# wemosD1mini_noSDmodule.net
KiCad netlist of a schematic drawn in EAGLE
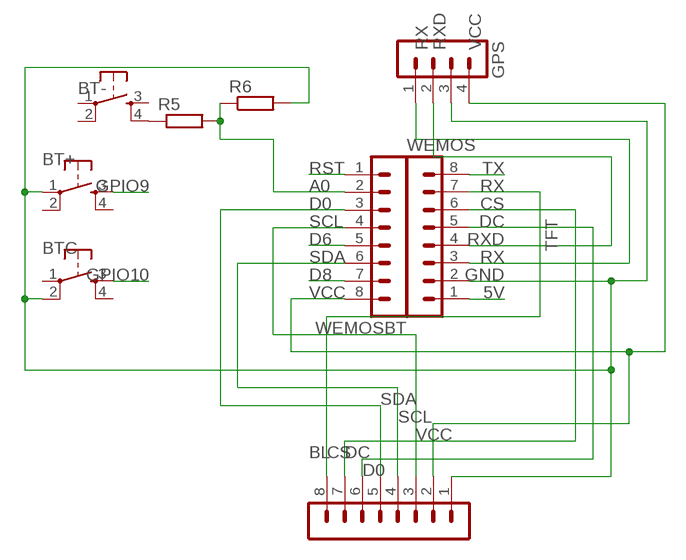
[diagram p0: schematic, sheet 1]

(export (version "E")
  (design (tool "Eeschema 10.0.6"))
  (components
    (comp (ref "BT+")
      (value "DTS-6")
      (footprint "eagle-import:DTS-6")
      (libsource (lib "eagle-import") (part "DTS-6"))
    )
    (comp (ref "BT-")
      (value "DTS-6")
      (footprint "eagle-import:DTS-6")
      (libsource (lib "eagle-import") (part "DTS-6"))
    )
    (comp (ref "BTC")
      (value "DTS-6")
      (footprint "eagle-import:DTS-6")
      (libsource (lib "eagle-import") (part "DTS-6"))
    )
    (comp (ref "GPS")
      (value "MA04-1")
      (footprint "eagle-import:MA04-1")
      (libsource (lib "eagle-import") (part "MA04-1"))
    )
    (comp (ref "R5")
      (value "R0207/10")
      (footprint "eagle-import:0207_10")
      (libsource (lib "eagle-import") (part "R0207/10"))
    )
    (comp (ref "R6")
      (value "R0207/10")
      (footprint "eagle-import:0207_10")
      (libsource (lib "eagle-import") (part "R0207/10"))
    )
    (comp (ref "TFT")
      (value "MA08-1W")
      (footprint "eagle-import:MA08-1W")
      (libsource (lib "eagle-import") (part "MA08-1W"))
    )
    (comp (ref "WEMOS")
      (value "MA08-1")
      (footprint "eagle-import:MA08-1")
      (libsource (lib "eagle-import") (part "MA08-1"))
    )
    (comp (ref "WEMOSBT")
      (value "MA08-1")
      (footprint "eagle-import:MA08-1")
      (libsource (lib "eagle-import") (part "MA08-1"))
    )
  )
  (nets
    (net (code "1") (name "/5V") (class "Default")
      (node (ref "WEMOS") (pin "1") (pinfunction "1_1") (pintype "passive"))
    )
    (net (code "2") (name "/A0") (class "Default")
      (node (ref "R5") (pin "2") (pinfunction "2_2") (pintype "passive"))
      (node (ref "R6") (pin "1") (pinfunction "1_1") (pintype "passive"))
      (node (ref "WEMOSBT") (pin "2") (pinfunction "2_2") (pintype "passive"))
    )
    (net (code "3") (name "/BL") (class "Default")
      (node (ref "TFT") (pin "8") (pinfunction "8_8") (pintype "passive"))
      (node (ref "WEMOS") (pin "7") (pinfunction "7_7") (pintype "passive"))
    )
    (net (code "4") (name "/CS") (class "Default")
      (node (ref "TFT") (pin "7") (pinfunction "7_7") (pintype "passive"))
      (node (ref "WEMOS") (pin "6") (pinfunction "6_6") (pintype "passive"))
    )
    (net (code "5") (name "/D0") (class "Default")
      (node (ref "TFT") (pin "5") (pinfunction "5_5") (pintype "passive"))
      (node (ref "WEMOSBT") (pin "3") (pinfunction "3_3") (pintype "passive"))
    )
    (net (code "6") (name "/D6") (class "Default")
      (node (ref "WEMOSBT") (pin "5") (pinfunction "5_5") (pintype "passive"))
    )
    (net (code "7") (name "/D8") (class "Default")
      (node (ref "WEMOSBT") (pin "7") (pinfunction "7_7") (pintype "passive"))
    )
    (net (code "8") (name "/DC") (class "Default")
      (node (ref "TFT") (pin "6") (pinfunction "6_6") (pintype "passive"))
      (node (ref "WEMOS") (pin "5") (pinfunction "5_5") (pintype "passive"))
    )
    (net (code "9") (name "/GND") (class "Default")
      (node (ref "BT+") (pin "1") (pinfunction "1_1") (pintype "passive"))
      (node (ref "BTC") (pin "2") (pinfunction "2_2") (pintype "passive"))
      (node (ref "GPS") (pin "3") (pinfunction "3_3") (pintype "passive"))
      (node (ref "R6") (pin "2") (pinfunction "2_2") (pintype "passive"))
      (node (ref "TFT") (pin "1") (pinfunction "1_1") (pintype "passive"))
      (node (ref "WEMOS") (pin "2") (pinfunction "2_2") (pintype "passive"))
    )
    (net (code "10") (name "/GPIO9") (class "Default")
      (node (ref "BT+") (pin "3") (pinfunction "3_3") (pintype "passive"))
    )
    (net (code "11") (name "/GPIO10") (class "Default")
      (node (ref "BTC") (pin "3") (pinfunction "3_3") (pintype "passive"))
    )
    (net (code "12") (name "/RST") (class "Default")
      (node (ref "WEMOSBT") (pin "1") (pinfunction "1_1") (pintype "passive"))
    )
    (net (code "13") (name "/RX") (class "Default")
      (node (ref "GPS") (pin "1") (pinfunction "1_1") (pintype "passive"))
      (node (ref "WEMOS") (pin "3") (pinfunction "3_3") (pintype "passive"))
    )
    (net (code "14") (name "/RXD") (class "Default")
      (node (ref "GPS") (pin "2") (pinfunction "2_2") (pintype "passive"))
      (node (ref "WEMOS") (pin "4") (pinfunction "4_4") (pintype "passive"))
    )
    (net (code "15") (name "/SCL") (class "Default")
      (node (ref "TFT") (pin "3") (pinfunction "3_3") (pintype "passive"))
      (node (ref "WEMOSBT") (pin "4") (pinfunction "4_4") (pintype "passive"))
    )
    (net (code "16") (name "/SDA") (class "Default")
      (node (ref "TFT") (pin "4") (pinfunction "4_4") (pintype "passive"))
      (node (ref "WEMOSBT") (pin "6") (pinfunction "6_6") (pintype "passive"))
    )
    (net (code "17") (name "/TX") (class "Default")
      (node (ref "WEMOS") (pin "8") (pinfunction "8_8") (pintype "passive"))
    )
    (net (code "18") (name "/VCC") (class "Default")
      (node (ref "GPS") (pin "4") (pinfunction "4_4") (pintype "passive"))
      (node (ref "TFT") (pin "2") (pinfunction "2_2") (pintype "passive"))
      (node (ref "WEMOSBT") (pin "8") (pinfunction "8_8") (pintype "passive"))
    )
    (net (code "19") (name "Net-(BT--Pad4)") (class "Default")
      (node (ref "BT-") (pin "4") (pinfunction "4_4") (pintype "passive"))
      (node (ref "R5") (pin "1") (pinfunction "1_1") (pintype "passive"))
    )
    (net (code "20") (name "unconnected-(BT+-Pad2)") (class "Default")
      (node (ref "BT+") (pin "2") (pinfunction "2_2") (pintype "passive"))
    )
    (net (code "21") (name "unconnected-(BT+-Pad4)") (class "Default")
      (node (ref "BT+") (pin "4") (pinfunction "4_4") (pintype "passive"))
    )
    (net (code "22") (name "unconnected-(BT--Pad1)") (class "Default")
      (node (ref "BT-") (pin "1") (pinfunction "1_1") (pintype "passive"))
    )
    (net (code "23") (name "unconnected-(BT--Pad2)") (class "Default")
      (node (ref "BT-") (pin "2") (pinfunction "2_2") (pintype "passive"))
    )
    (net (code "24") (name "unconnected-(BT--Pad3)") (class "Default")
      (node (ref "BT-") (pin "3") (pinfunction "3_3") (pintype "passive"))
    )
    (net (code "25") (name "unconnected-(BTC-Pad1)") (class "Default")
      (node (ref "BTC") (pin "1") (pinfunction "1_1") (pintype "passive"))
    )
    (net (code "26") (name "unconnected-(BTC-Pad4)") (class "Default")
      (node (ref "BTC") (pin "4") (pinfunction "4_4") (pintype "passive"))
    )
  )
)
